# eBOOK-UPDATE_v3.net
KiCad netlist of a schematic drawn in EAGLE
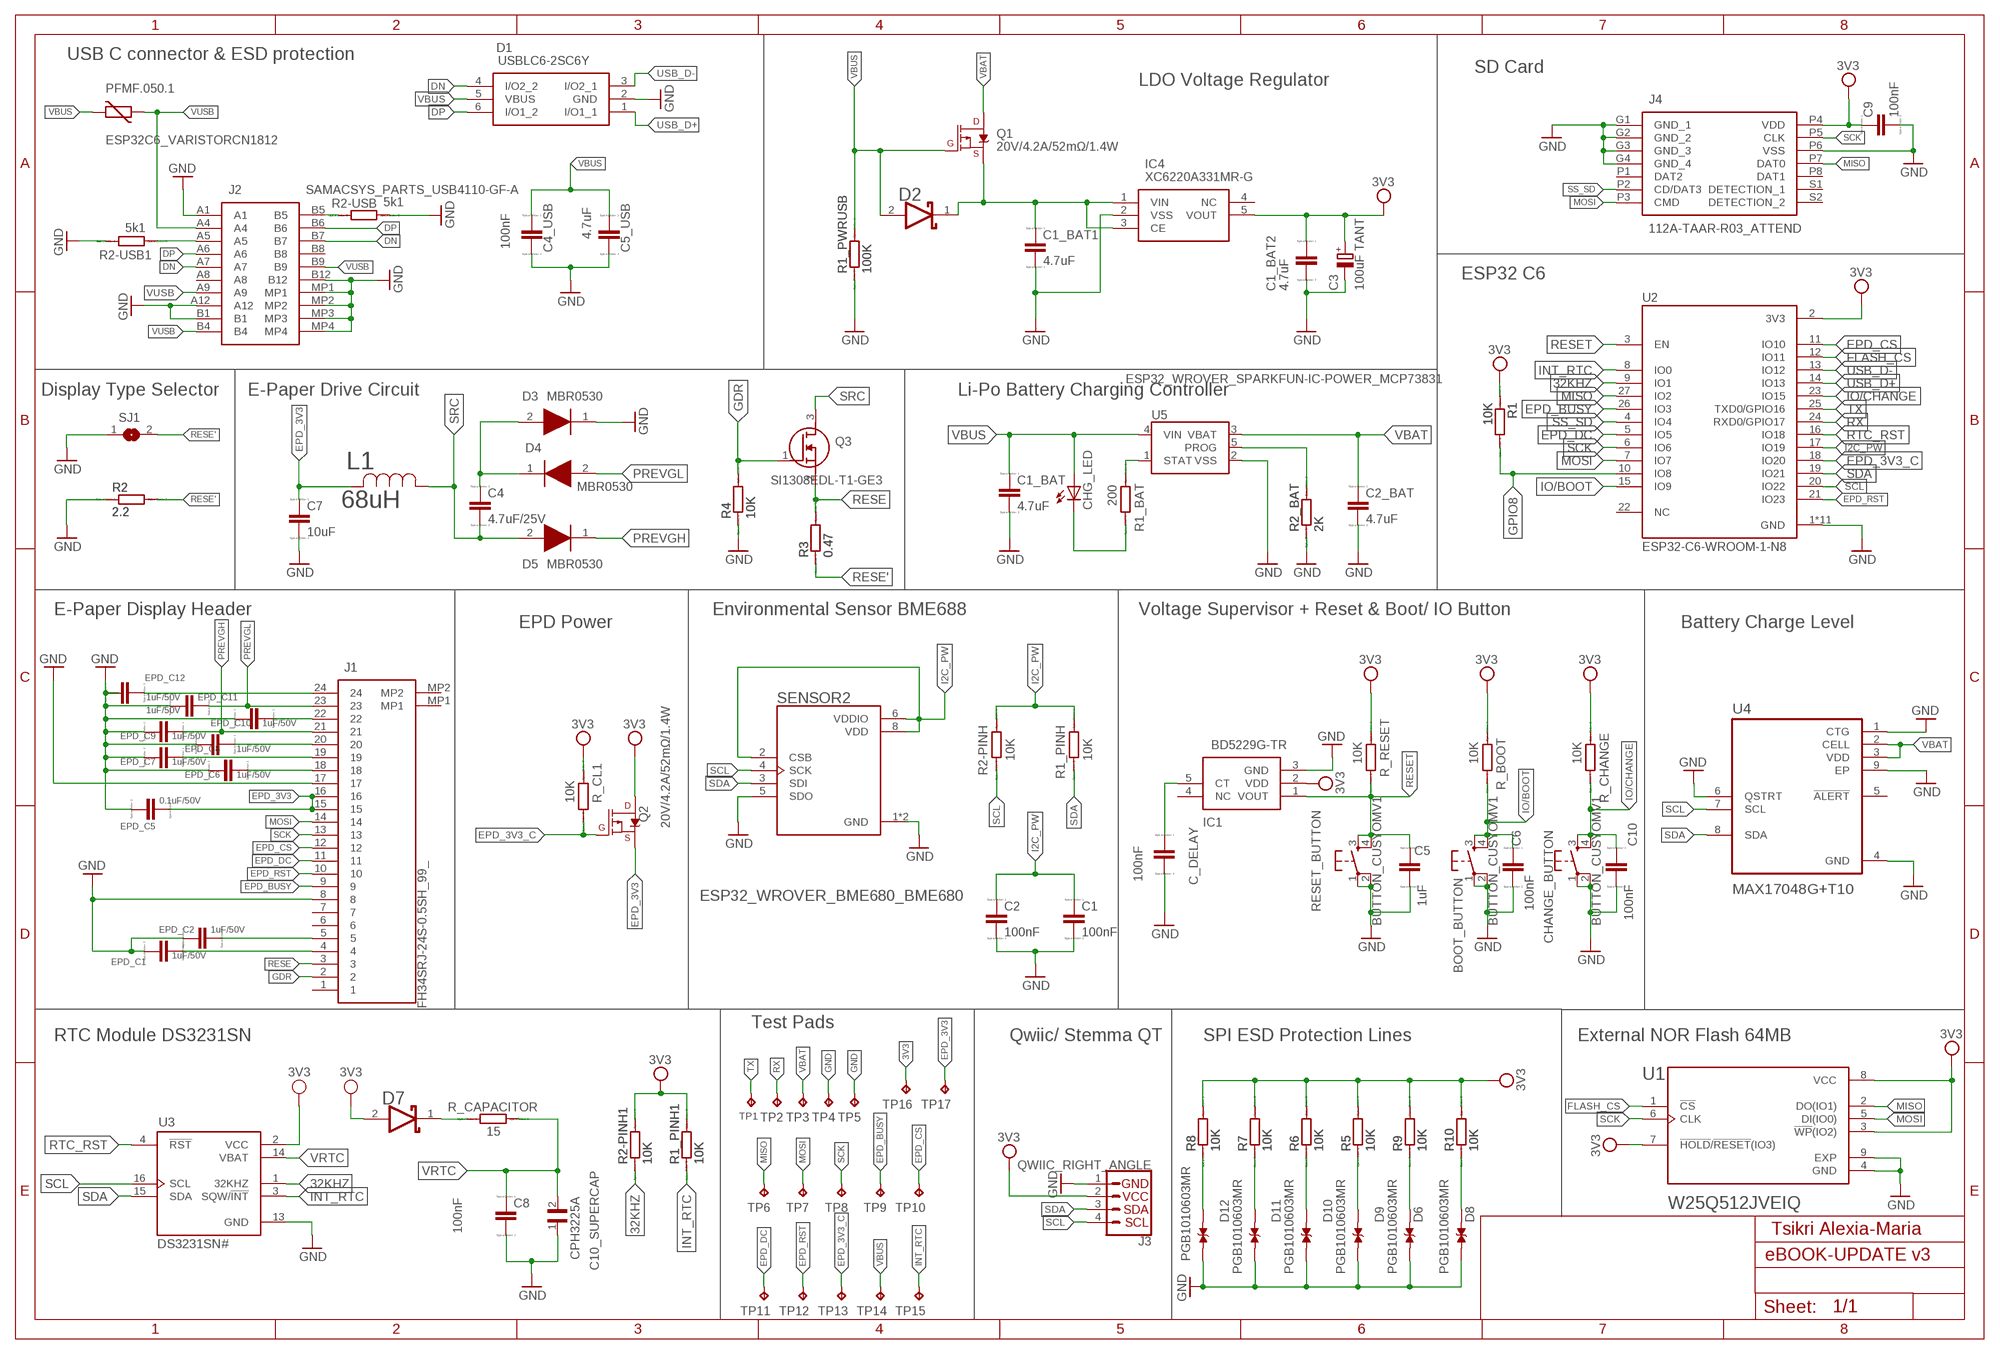
[diagram p0: schematic, sheet 1]

(export (version "E")
  (design (tool "Eeschema 10.0.6"))
  (components
    (comp (ref "BOOT_BUTTON")
      (value "BUTTON_CUSYOMV1")
      (footprint "eagle-import:MYBUTTON")
      (libsource (lib "eagle-import") (part "BUTTON_CUSYOMV1"))
    )
    (comp (ref "C1")
      (value "100nF")
      (footprint "eagle-import:ESP32_WROVER_EAGLE-LTSPICE_C0402")
      (libsource (lib "eagle-import") (part "ESP32_WROVER_EAGLE-LTSPICE_CC0402"))
    )
    (comp (ref "C1_BAT")
      (value "4.7uF")
      (footprint "eagle-import:ESP32_WROVER_EAGLE-LTSPICE_C0402")
      (libsource (lib "eagle-import") (part "ESP32_WROVER_EAGLE-LTSPICE_CC0402"))
    )
    (comp (ref "C1_BAT1")
      (value "4.7uF")
      (footprint "eagle-import:ESP32_WROVER_EAGLE-LTSPICE_C0402")
      (libsource (lib "eagle-import") (part "ESP32_WROVER_EAGLE-LTSPICE_CC0402"))
    )
    (comp (ref "C1_BAT2")
      (value "4.7uF")
      (footprint "eagle-import:ESP32_WROVER_EAGLE-LTSPICE_C0402")
      (libsource (lib "eagle-import") (part "ESP32_WROVER_EAGLE-LTSPICE_CC0402"))
    )
    (comp (ref "C2")
      (value "100nF")
      (footprint "eagle-import:ESP32_WROVER_EAGLE-LTSPICE_C0402")
      (libsource (lib "eagle-import") (part "ESP32_WROVER_EAGLE-LTSPICE_CC0402"))
    )
    (comp (ref "C2_BAT")
      (value "4.7uF")
      (footprint "eagle-import:ESP32_WROVER_EAGLE-LTSPICE_C0402")
      (libsource (lib "eagle-import") (part "ESP32_WROVER_EAGLE-LTSPICE_CC0402"))
    )
    (comp (ref "C3")
      (value "100uF TANT")
      (footprint "eagle-import:RCL_CT3528")
      (libsource (lib "eagle-import") (part "RCL_CPOL-EUCT3528"))
    )
    (comp (ref "C4")
      (value "4.7uF/25V")
      (footprint "eagle-import:ESP32_WROVER_EAGLE-LTSPICE_C0402")
      (libsource (lib "eagle-import") (part "ESP32_WROVER_EAGLE-LTSPICE_CC0402"))
    )
    (comp (ref "C4_USB")
      (value "100nF")
      (footprint "eagle-import:ESP32_WROVER_EAGLE-LTSPICE_C0402")
      (libsource (lib "eagle-import") (part "ESP32_WROVER_EAGLE-LTSPICE_CC0402"))
    )
    (comp (ref "C5")
      (value "1uF")
      (footprint "eagle-import:ESP32_WROVER_EAGLE-LTSPICE_C0402")
      (libsource (lib "eagle-import") (part "ESP32_WROVER_EAGLE-LTSPICE_CC0402"))
    )
    (comp (ref "C5_USB")
      (value "4.7uF")
      (footprint "eagle-import:ESP32_WROVER_EAGLE-LTSPICE_C0402")
      (libsource (lib "eagle-import") (part "ESP32_WROVER_EAGLE-LTSPICE_CC0402"))
    )
    (comp (ref "C6")
      (value "100nF")
      (footprint "eagle-import:ESP32_WROVER_EAGLE-LTSPICE_C0402")
      (libsource (lib "eagle-import") (part "ESP32_WROVER_EAGLE-LTSPICE_CC0402"))
    )
    (comp (ref "C7")
      (value "10uF")
      (footprint "eagle-import:ESP32_WROVER_EAGLE-LTSPICE_C0402")
      (libsource (lib "eagle-import") (part "ESP32_WROVER_EAGLE-LTSPICE_CC0402"))
    )
    (comp (ref "C8")
      (value "100nF")
      (footprint "eagle-import:ESP32_WROVER_EAGLE-LTSPICE_C0402")
      (libsource (lib "eagle-import") (part "ESP32_WROVER_EAGLE-LTSPICE_CC0402"))
    )
    (comp (ref "C9")
      (value "100nF")
      (footprint "eagle-import:ESP32_WROVER_EAGLE-LTSPICE_C0402")
      (libsource (lib "eagle-import") (part "ESP32_WROVER_EAGLE-LTSPICE_CC0402"))
    )
    (comp (ref "C10")
      (value "100nF")
      (footprint "eagle-import:ESP32_WROVER_EAGLE-LTSPICE_C0402")
      (libsource (lib "eagle-import") (part "ESP32_WROVER_EAGLE-LTSPICE_CC0402"))
    )
    (comp (ref "C10_SUPERCAP")
      (value "CPH3225A")
      (footprint "eagle-import:CAPCP3225X100N")
      (fields (field (name "MF") "Seiko Instruments"))
      (libsource (lib "eagle-import") (part "CPH3225A"))
    )
    (comp (ref "CHANGE_BUTTON")
      (value "BUTTON_CUSYOMV1")
      (footprint "eagle-import:MYBUTTON")
      (libsource (lib "eagle-import") (part "BUTTON_CUSYOMV1"))
    )
    (comp (ref "CHG_LED")
      (value "ADAFRUIT_LEDCHIP-LED0603")
      (footprint "eagle-import:ADAFRUIT_CHIP-LED0603")
      (libsource (lib "eagle-import") (part "ADAFRUIT_LEDCHIP-LED0603"))
    )
    (comp (ref "C_DELAY")
      (value "100nF")
      (footprint "eagle-import:ESP32_WROVER_EAGLE-LTSPICE_C0402")
      (libsource (lib "eagle-import") (part "ESP32_WROVER_EAGLE-LTSPICE_CC0402"))
    )
    (comp (ref "D1")
      (value "USBLC6-2SC6Y")
      (footprint "eagle-import:SOT95P280X145-6N")
      (fields (field (name "MF") "STMicroelectronics"))
      (libsource (lib "eagle-import") (part "USBLC6-2SC6Y"))
    )
    (comp (ref "D2")
      (value "ESP32_WROVER_AVX---SD0805S020S1R0_AVX_SD0805S020S1R0_0_0AVX_SD0805S020S1R0_0_0")
      (footprint "eagle-import:ESP32_WROVER_AVX---SD0805S020S1R0_AVX_SD0805S020S1R0_0")
      (fields
        (field (name "DIGIKEY_PART_NUMBER") "478-7800-1-ND")
        (field (name "MF") "AVX")
        (field (name "MOUSER_PART_NUMBER") "581-SD0805S020S1R0")
      )
      (libsource (lib "eagle-import") (part "ESP32_WROVER_AVX---SD0805S020S1R0_AVX_SD0805S020S1R0_0_0AVX_SD0805S020S1R0_0_0"))
    )
    (comp (ref "D3")
      (value "MBR0530")
      (footprint "eagle-import:SOD3716X135N")
      (fields (field (name "MF") "ON Semiconductor"))
      (libsource (lib "eagle-import") (part "MBR0530"))
    )
    (comp (ref "D4")
      (value "MBR0530")
      (footprint "eagle-import:SOD3716X135N")
      (fields (field (name "MF") "ON Semiconductor"))
      (libsource (lib "eagle-import") (part "MBR0530"))
    )
    (comp (ref "D5")
      (value "MBR0530")
      (footprint "eagle-import:SOD3716X135N")
      (fields (field (name "MF") "ON Semiconductor"))
      (libsource (lib "eagle-import") (part "MBR0530"))
    )
    (comp (ref "D6")
      (value "PGB1010603MR")
      (footprint "eagle-import:DIOC1608X36N")
      (fields (field (name "MF") "Littelfuse Inc."))
      (libsource (lib "eagle-import") (part "PGB1010603MR"))
    )
    (comp (ref "D7")
      (value "ESP32_WROVER_AVX---SD0805S020S1R0_AVX_SD0805S020S1R0_0_0AVX_SD0805S020S1R0_0_0")
      (footprint "eagle-import:ESP32_WROVER_AVX---SD0805S020S1R0_AVX_SD0805S020S1R0_0")
      (fields
        (field (name "DIGIKEY_PART_NUMBER") "478-7800-1-ND")
        (field (name "MF") "AVX")
        (field (name "MOUSER_PART_NUMBER") "581-SD0805S020S1R0")
      )
      (libsource (lib "eagle-import") (part "ESP32_WROVER_AVX---SD0805S020S1R0_AVX_SD0805S020S1R0_0_0AVX_SD0805S020S1R0_0_0"))
    )
    (comp (ref "D8")
      (value "PGB1010603MR")
      (footprint "eagle-import:DIOC1608X36N")
      (fields (field (name "MF") "Littelfuse Inc."))
      (libsource (lib "eagle-import") (part "PGB1010603MR"))
    )
    (comp (ref "D9")
      (value "PGB1010603MR")
      (footprint "eagle-import:DIOC1608X36N")
      (fields (field (name "MF") "Littelfuse Inc."))
      (libsource (lib "eagle-import") (part "PGB1010603MR"))
    )
    (comp (ref "D10")
      (value "PGB1010603MR")
      (footprint "eagle-import:DIOC1608X36N")
      (fields (field (name "MF") "Littelfuse Inc."))
      (libsource (lib "eagle-import") (part "PGB1010603MR"))
    )
    (comp (ref "D11")
      (value "PGB1010603MR")
      (footprint "eagle-import:DIOC1608X36N")
      (fields (field (name "MF") "Littelfuse Inc."))
      (libsource (lib "eagle-import") (part "PGB1010603MR"))
    )
    (comp (ref "D12")
      (value "PGB1010603MR")
      (footprint "eagle-import:DIOC1608X36N")
      (fields (field (name "MF") "Littelfuse Inc."))
      (libsource (lib "eagle-import") (part "PGB1010603MR"))
    )
    (comp (ref "EPD_C1")
      (value "1uF/50V")
      (footprint "eagle-import:ESP32_WROVER_EAGLE-LTSPICE_C0402")
      (libsource (lib "eagle-import") (part "ESP32_WROVER_EAGLE-LTSPICE_CC0402"))
    )
    (comp (ref "EPD_C2")
      (value "1uF/50V")
      (footprint "eagle-import:ESP32_WROVER_EAGLE-LTSPICE_C0402")
      (libsource (lib "eagle-import") (part "ESP32_WROVER_EAGLE-LTSPICE_CC0402"))
    )
    (comp (ref "EPD_C5")
      (value "0.1uF/50V")
      (footprint "eagle-import:ESP32_WROVER_EAGLE-LTSPICE_C0402")
      (libsource (lib "eagle-import") (part "ESP32_WROVER_EAGLE-LTSPICE_CC0402"))
    )
    (comp (ref "EPD_C6")
      (value "1uF/50V")
      (footprint "eagle-import:ESP32_WROVER_EAGLE-LTSPICE_C0402")
      (libsource (lib "eagle-import") (part "ESP32_WROVER_EAGLE-LTSPICE_CC0402"))
    )
    (comp (ref "EPD_C7")
      (value "1uF/50V")
      (footprint "eagle-import:ESP32_WROVER_EAGLE-LTSPICE_C0402")
      (libsource (lib "eagle-import") (part "ESP32_WROVER_EAGLE-LTSPICE_CC0402"))
    )
    (comp (ref "EPD_C8")
      (value "1uF/50V")
      (footprint "eagle-import:ESP32_WROVER_EAGLE-LTSPICE_C0402")
      (libsource (lib "eagle-import") (part "ESP32_WROVER_EAGLE-LTSPICE_CC0402"))
    )
    (comp (ref "EPD_C9")
      (value "1uF/50V")
      (footprint "eagle-import:ESP32_WROVER_EAGLE-LTSPICE_C0402")
      (libsource (lib "eagle-import") (part "ESP32_WROVER_EAGLE-LTSPICE_CC0402"))
    )
    (comp (ref "EPD_C10")
      (value "1uF/50V")
      (footprint "eagle-import:ESP32_WROVER_EAGLE-LTSPICE_C0402")
      (libsource (lib "eagle-import") (part "ESP32_WROVER_EAGLE-LTSPICE_CC0402"))
    )
    (comp (ref "EPD_C11")
      (value "1uF/50V")
      (footprint "eagle-import:ESP32_WROVER_EAGLE-LTSPICE_C0402")
      (libsource (lib "eagle-import") (part "ESP32_WROVER_EAGLE-LTSPICE_CC0402"))
    )
    (comp (ref "EPD_C12")
      (value "1uF/50V")
      (footprint "eagle-import:ESP32_WROVER_EAGLE-LTSPICE_C0402")
      (libsource (lib "eagle-import") (part "ESP32_WROVER_EAGLE-LTSPICE_CC0402"))
    )
    (comp (ref "IC1")
      (value "BD5229G-TR")
      (footprint "eagle-import:SOT95P280X125-5N")
      (fields (field (name "MOUSER_PART_NUMBER") "755-BD5229G-TR"))
      (libsource (lib "eagle-import") (part "BD5229G-TR"))
    )
    (comp (ref "IC4")
      (value "XC6220A331MR-G")
      (footprint "eagle-import:SOT95P280X120-5N")
      (fields (field (name "MOUSER_PART_NUMBER") "865-XC6220A331MR-G"))
      (libsource (lib "eagle-import") (part "XC6220A331MR-G"))
    )
    (comp (ref "J1")
      (value "FH34SRJ-24S-0.5SH_99_")
      (footprint "eagle-import:FH34SRJ24S05SH99")
      (fields
        (field (name "MANUFACTURER_PART_NUMBER") "FH34SRJ-24S-0.5SH(99)")
        (field (name "MOUSER_PART_NUMBER") "798-FH34SRJ24S05SH99")
      )
      (libsource (lib "eagle-import") (part "FH34SRJ-24S-0.5SH_99_"))
    )
    (comp (ref "J2")
      (value "SAMACSYS_PARTS_USB4110-GF-A")
      (footprint "eagle-import:SAMACSYS_PARTS_USB4110GFA")
      (fields
        (field (name "MANUFACTURER_PART_NUMBER") "USB4110-GF-A")
        (field (name "MOUSER_PART_NUMBER") "640-USB4110-GF-A")
      )
      (libsource (lib "eagle-import") (part "SAMACSYS_PARTS_USB4110-GF-A"))
    )
    (comp (ref "J3")
      (value "QWIIC_RIGHT_ANGLE")
      (footprint "eagle-import:JST04_1MM_RA")
      (libsource (lib "eagle-import") (part "QWIIC_CONNECTORJS-1MM"))
    )
    (comp (ref "J4")
      (value "112A-TAAR-R03_ATTEND")
      (footprint "eagle-import:112ATAARR03ATTEND")
      (fields (field (name "MANUFACTURER_PART_NUMBER") "112A-TAAR-R03 ATTEND"))
      (libsource (lib "eagle-import") (part "112A-TAAR-R03_ATTEND"))
    )
    (comp (ref "L1")
      (value "68uH")
      (footprint "eagle-import:IND_4828-WE-TPC_WRE")
      (fields
        (field (name "MANUFACTURER_PART_NUMBER") "744043680")
        (field (name "COPYRIGHT") "Copyright (C) 2024 Ultra Librarian. All rights reserved.")
      )
      (libsource (lib "eagle-import") (part "744043680IND_4828-WE-TPC_WRE"))
    )
    (comp (ref "PFMF.050.1")
      (value "ESP32C6_VARISTORCN1812")
      (footprint "eagle-import:ESP32C6_VARISTOR_CT_CN1812")
      (libsource (lib "eagle-import") (part "ESP32C6_VARISTORCN1812"))
    )
    (comp (ref "Q1")
      (value "20V/4.2A/52mΩ/1.4W")
      (footprint "eagle-import:ESP32_WROVER_SPARKFUN-DISCRETESEMI_SOT23-3")
      (libsource (lib "eagle-import") (part "ESP32_WROVER_SPARKFUN-DISCRETESEMI_MOSFET_PCH-DMG2305UX-7"))
    )
    (comp (ref "Q2")
      (value "20V/4.2A/52mΩ/1.4W")
      (footprint "eagle-import:ESP32_WROVER_SPARKFUN-DISCRETESEMI_SOT23-3")
      (libsource (lib "eagle-import") (part "ESP32_WROVER_SPARKFUN-DISCRETESEMI_MOSFET_PCH-DMG2305UX-7"))
    )
    (comp (ref "Q3")
      (value "SI1308EDL-T1-GE3")
      (footprint "eagle-import:SOT65P210X110-3N")
      (fields (field (name "MF") "Vishay Siliconix"))
      (libsource (lib "eagle-import") (part "SI1308EDL-T1-GE3"))
    )
    (comp (ref "R1")
      (value "10K")
      (footprint "eagle-import:ESP32_WROVER_EAGLE-LTSPICE_R0402")
      (libsource (lib "eagle-import") (part "ESP32_WROVER_EAGLE-LTSPICE_RR0402"))
    )
    (comp (ref "R1_BAT")
      (value "200")
      (footprint "eagle-import:ESP32_WROVER_EAGLE-LTSPICE_R0402")
      (libsource (lib "eagle-import") (part "ESP32_WROVER_EAGLE-LTSPICE_RR0402"))
    )
    (comp (ref "R1_PINH")
      (value "10K")
      (footprint "eagle-import:ESP32_WROVER_EAGLE-LTSPICE_R0402")
      (libsource (lib "eagle-import") (part "ESP32_WROVER_EAGLE-LTSPICE_RR0402"))
    )
    (comp (ref "R1_PINH1")
      (value "10K")
      (footprint "eagle-import:ESP32_WROVER_EAGLE-LTSPICE_R0402")
      (libsource (lib "eagle-import") (part "ESP32_WROVER_EAGLE-LTSPICE_RR0402"))
    )
    (comp (ref "R1_PWRUSB")
      (value "100K")
      (footprint "eagle-import:ESP32_WROVER_EAGLE-LTSPICE_R0402")
      (libsource (lib "eagle-import") (part "ESP32_WROVER_EAGLE-LTSPICE_RR0402"))
    )
    (comp (ref "R2")
      (value "2.2")
      (footprint "eagle-import:ESP32_WROVER_EAGLE-LTSPICE_R0402")
      (libsource (lib "eagle-import") (part "ESP32_WROVER_EAGLE-LTSPICE_RR0402"))
    )
    (comp (ref "R2-PINH")
      (value "10K")
      (footprint "eagle-import:ESP32_WROVER_EAGLE-LTSPICE_R0402")
      (libsource (lib "eagle-import") (part "ESP32_WROVER_EAGLE-LTSPICE_RR0402"))
    )
    (comp (ref "R2-PINH1")
      (value "10K")
      (footprint "eagle-import:ESP32_WROVER_EAGLE-LTSPICE_R0402")
      (libsource (lib "eagle-import") (part "ESP32_WROVER_EAGLE-LTSPICE_RR0402"))
    )
    (comp (ref "R2-USB")
      (value "5k1")
      (footprint "eagle-import:ESP32_WROVER_EAGLE-LTSPICE_R0402")
      (libsource (lib "eagle-import") (part "ESP32_WROVER_EAGLE-LTSPICE_RR0402"))
    )
    (comp (ref "R2-USB1")
      (value "5k1")
      (footprint "eagle-import:ESP32_WROVER_EAGLE-LTSPICE_R0402")
      (libsource (lib "eagle-import") (part "ESP32_WROVER_EAGLE-LTSPICE_RR0402"))
    )
    (comp (ref "R2_BAT")
      (value "2K")
      (footprint "eagle-import:ESP32_WROVER_EAGLE-LTSPICE_R0402")
      (libsource (lib "eagle-import") (part "ESP32_WROVER_EAGLE-LTSPICE_RR0402"))
    )
    (comp (ref "R3")
      (value "0.47")
      (footprint "eagle-import:ESP32_WROVER_EAGLE-LTSPICE_R0402")
      (libsource (lib "eagle-import") (part "ESP32_WROVER_EAGLE-LTSPICE_RR0402"))
    )
    (comp (ref "R4")
      (value "10K")
      (footprint "eagle-import:ESP32_WROVER_EAGLE-LTSPICE_R0402")
      (libsource (lib "eagle-import") (part "ESP32_WROVER_EAGLE-LTSPICE_RR0402"))
    )
    (comp (ref "R5")
      (value "10K")
      (footprint "eagle-import:ESP32_WROVER_EAGLE-LTSPICE_R0402")
      (libsource (lib "eagle-import") (part "ESP32_WROVER_EAGLE-LTSPICE_RR0402"))
    )
    (comp (ref "R6")
      (value "10K")
      (footprint "eagle-import:ESP32_WROVER_EAGLE-LTSPICE_R0402")
      (libsource (lib "eagle-import") (part "ESP32_WROVER_EAGLE-LTSPICE_RR0402"))
    )
    (comp (ref "R7")
      (value "10K")
      (footprint "eagle-import:ESP32_WROVER_EAGLE-LTSPICE_R0402")
      (libsource (lib "eagle-import") (part "ESP32_WROVER_EAGLE-LTSPICE_RR0402"))
    )
    (comp (ref "R8")
      (value "10K")
      (footprint "eagle-import:ESP32_WROVER_EAGLE-LTSPICE_R0402")
      (libsource (lib "eagle-import") (part "ESP32_WROVER_EAGLE-LTSPICE_RR0402"))
    )
    (comp (ref "R9")
      (value "10K")
      (footprint "eagle-import:ESP32_WROVER_EAGLE-LTSPICE_R0402")
      (libsource (lib "eagle-import") (part "ESP32_WROVER_EAGLE-LTSPICE_RR0402"))
    )
    (comp (ref "R10")
      (value "10K")
      (footprint "eagle-import:ESP32_WROVER_EAGLE-LTSPICE_R0402")
      (libsource (lib "eagle-import") (part "ESP32_WROVER_EAGLE-LTSPICE_RR0402"))
    )
    (comp (ref "RESET_BUTTON")
      (value "BUTTON_CUSYOMV1")
      (footprint "eagle-import:MYBUTTON")
      (libsource (lib "eagle-import") (part "BUTTON_CUSYOMV1"))
    )
    (comp (ref "R_BOOT")
      (value "10K")
      (footprint "eagle-import:ESP32_WROVER_EAGLE-LTSPICE_R0402")
      (libsource (lib "eagle-import") (part "ESP32_WROVER_EAGLE-LTSPICE_RR0402"))
    )
    (comp (ref "R_CAPACITOR")
      (value "15")
      (footprint "eagle-import:ESP32_WROVER_EAGLE-LTSPICE_R0402")
      (libsource (lib "eagle-import") (part "ESP32_WROVER_EAGLE-LTSPICE_RR0402"))
    )
    (comp (ref "R_CHANGE")
      (value "10K")
      (footprint "eagle-import:ESP32_WROVER_EAGLE-LTSPICE_R0402")
      (libsource (lib "eagle-import") (part "ESP32_WROVER_EAGLE-LTSPICE_RR0402"))
    )
    (comp (ref "R_CL1")
      (value "10K")
      (footprint "eagle-import:ESP32_WROVER_EAGLE-LTSPICE_R0402")
      (libsource (lib "eagle-import") (part "ESP32_WROVER_EAGLE-LTSPICE_RR0402"))
    )
    (comp (ref "R_RESET")
      (value "10K")
      (footprint "eagle-import:ESP32_WROVER_EAGLE-LTSPICE_R0402")
      (libsource (lib "eagle-import") (part "ESP32_WROVER_EAGLE-LTSPICE_RR0402"))
    )
    (comp (ref "SENSOR2")
      (value "ESP32_WROVER_BME680_BME680")
      (footprint "eagle-import:ESP32_WROVER_BME680_PSON80P300X300X100-8N")
      (fields (field (name "MF") "Bosch Sensortec") (field (name "MP") "BME680"))
      (libsource (lib "eagle-import") (part "ESP32_WROVER_BME680_BME680"))
    )
    (comp (ref "SJ1") (value "SJ") (footprint "eagle-import:SJ") (libsource (lib "eagle-import") (part "SJ")))
    (comp (ref "TP1")
      (value "TPTP20R")
      (footprint "eagle-import:TP20R")
      (libsource (lib "eagle-import") (part "TPTP20R"))
    )
    (comp (ref "TP2")
      (value "TPTP20R")
      (footprint "eagle-import:TP20R")
      (libsource (lib "eagle-import") (part "TPTP20R"))
    )
    (comp (ref "TP3")
      (value "TPTP20R")
      (footprint "eagle-import:TP20R")
      (libsource (lib "eagle-import") (part "TPTP20R"))
    )
    (comp (ref "TP4")
      (value "TPTP20R")
      (footprint "eagle-import:TP20R")
      (libsource (lib "eagle-import") (part "TPTP20R"))
    )
    (comp (ref "TP5")
      (value "TPTP20R")
      (footprint "eagle-import:TP20R")
      (libsource (lib "eagle-import") (part "TPTP20R"))
    )
    (comp (ref "TP6")
      (value "TPTP20R")
      (footprint "eagle-import:TP20R")
      (libsource (lib "eagle-import") (part "TPTP20R"))
    )
    (comp (ref "TP7")
      (value "TPTP20R")
      (footprint "eagle-import:TP20R")
      (libsource (lib "eagle-import") (part "TPTP20R"))
    )
    (comp (ref "TP8")
      (value "TPTP20R")
      (footprint "eagle-import:TP20R")
      (libsource (lib "eagle-import") (part "TPTP20R"))
    )
    (comp (ref "TP9")
      (value "TPTP20R")
      (footprint "eagle-import:TP20R")
      (libsource (lib "eagle-import") (part "TPTP20R"))
    )
    (comp (ref "TP10")
      (value "TPTP20R")
      (footprint "eagle-import:TP20R")
      (libsource (lib "eagle-import") (part "TPTP20R"))
    )
    (comp (ref "TP11")
      (value "TPTP20R")
      (footprint "eagle-import:TP20R")
      (libsource (lib "eagle-import") (part "TPTP20R"))
    )
    (comp (ref "TP12")
      (value "TPTP20R")
      (footprint "eagle-import:TP20R")
      (libsource (lib "eagle-import") (part "TPTP20R"))
    )
    (comp (ref "TP13")
      (value "TPTP20R")
      (footprint "eagle-import:TP20R")
      (libsource (lib "eagle-import") (part "TPTP20R"))
    )
    (comp (ref "TP14")
      (value "TPTP20R")
      (footprint "eagle-import:TP20R")
      (libsource (lib "eagle-import") (part "TPTP20R"))
    )
    (comp (ref "TP15")
      (value "TPTP20R")
      (footprint "eagle-import:TP20R")
      (libsource (lib "eagle-import") (part "TPTP20R"))
    )
    (comp (ref "TP16")
      (value "TPTP20R")
      (footprint "eagle-import:TP20R")
      (libsource (lib "eagle-import") (part "TPTP20R"))
    )
    (comp (ref "TP17")
      (value "TPTP20R")
      (footprint "eagle-import:TP20R")
      (libsource (lib "eagle-import") (part "TPTP20R"))
    )
    (comp (ref "U1")
      (value "W25Q512JVEIQ")
      (footprint "eagle-import:SON127P600X800X80-9N")
      (fields (field (name "MF") "Winbond Electronics"))
      (libsource (lib "eagle-import") (part "W25Q512JVEIQ"))
    )
    (comp (ref "U2")
      (value "ESP32-C6-WROOM-1-N8")
      (footprint "eagle-import:XCVR_ESP32-C6-WROOM-1-N8")
      (fields (field (name "MF") "Espressif Systems"))
      (libsource (lib "eagle-import") (part "ESP32-C6-WROOM-1-N8"))
    )
    (comp (ref "U3")
      (value "DS3231SN#")
      (footprint "eagle-import:SOIC127P1032X265-16N")
      (fields (field (name "MF") "Maxim Integrated Products"))
      (libsource (lib "eagle-import") (part "DS3231SN#"))
    )
    (comp (ref "U4")
      (value "MAX17048G+T10")
      (footprint "eagle-import:SON50P200X200X80-9N")
      (fields (field (name "MF") "Analog Devices"))
      (libsource (lib "eagle-import") (part "MAX17048G+T10"))
    )
    (comp (ref "U5")
      (value "ESP32_WROVER_SPARKFUN-IC-POWER_MCP73831")
      (footprint "eagle-import:ESP32_WROVER_SPARKFUN-IC-POWER_SOT23-5")
      (libsource (lib "eagle-import") (part "ESP32_WROVER_SPARKFUN-IC-POWER_MCP73831"))
    )
  )
  (nets
    (net (code "1") (name "3V3") (class "Default")
      (node (ref "C1_BAT2") (pin "1") (pinfunction "1_1") (pintype "passive"))
      (node (ref "C3") (pin "+") (pinfunction "+_+") (pintype "passive"))
      (node (ref "C9") (pin "1") (pinfunction "1_1") (pintype "passive"))
      (node (ref "D7") (pin "2") (pinfunction "ANODE_2") (pintype "bidirectional"))
      (node (ref "IC1") (pin "2") (pinfunction "VDD_2") (pintype "bidirectional"))
      (node (ref "IC4") (pin "5") (pinfunction "VOUT_5") (pintype "bidirectional"))
      (node (ref "J3") (pin "2") (pinfunction "2_2") (pintype "power_in"))
      (node (ref "J4") (pin "P4") (pinfunction "VDD_P4") (pintype "bidirectional"))
      (node (ref "Q2") (pin "3") (pinfunction "D_3") (pintype "bidirectional"))
      (node (ref "R1") (pin "1") (pinfunction "1_1") (pintype "passive"))
      (node (ref "R10") (pin "2") (pinfunction "2_2") (pintype "passive"))
      (node (ref "R1_PINH1") (pin "2") (pinfunction "2_2") (pintype "passive"))
      (node (ref "R2-PINH1") (pin "2") (pinfunction "2_2") (pintype "passive"))
      (node (ref "R5") (pin "2") (pinfunction "2_2") (pintype "passive"))
      (node (ref "R6") (pin "2") (pinfunction "2_2") (pintype "passive"))
      (node (ref "R7") (pin "2") (pinfunction "2_2") (pintype "passive"))
      (node (ref "R8") (pin "2") (pinfunction "2_2") (pintype "passive"))
      (node (ref "R9") (pin "2") (pinfunction "2_2") (pintype "passive"))
      (node (ref "R_BOOT") (pin "2") (pinfunction "2_2") (pintype "passive"))
      (node (ref "R_CHANGE") (pin "2") (pinfunction "2_2") (pintype "passive"))
      (node (ref "R_CL1") (pin "2") (pinfunction "2_2") (pintype "passive"))
      (node (ref "R_RESET") (pin "2") (pinfunction "2_2") (pintype "passive"))
      (node (ref "TP16") (pin "TP") (pinfunction "TP_TP") (pintype "input"))
      (node (ref "U1") (pin "3") (pinfunction "~{WP}(IO2)_3") (pintype "bidirectional"))
      (node (ref "U1") (pin "7") (pinfunction "~{HOLD}/~{RESET}(IO3)_7") (pintype "bidirectional"))
      (node (ref "U1") (pin "8") (pinfunction "VCC_8") (pintype "power_in"))
      (node (ref "U2") (pin "2") (pinfunction "3V3_2") (pintype "power_in"))
      (node (ref "U3") (pin "2") (pinfunction "VCC_2") (pintype "power_in"))
    )
    (net (code "2") (name "32KHZ") (class "Default")
      (node (ref "R2-PINH1") (pin "1") (pinfunction "1_1") (pintype "passive"))
      (node (ref "U2") (pin "9") (pinfunction "IO1_9") (pintype "bidirectional"))
      (node (ref "U3") (pin "1") (pinfunction "32KHZ_1") (pintype "output"))
    )
    (net (code "3") (name "DN") (class "Default")
      (node (ref "D1") (pin "4") (pinfunction "I/O2_2_4") (pintype "bidirectional"))
      (node (ref "J2") (pin "A7") (pinfunction "A7_A7") (pintype "bidirectional"))
      (node (ref "J2") (pin "B7") (pinfunction "B7_B7") (pintype "bidirectional"))
    )
    (net (code "4") (name "DP") (class "Default")
      (node (ref "D1") (pin "6") (pinfunction "I/O1_2_6") (pintype "bidirectional"))
      (node (ref "J2") (pin "A6") (pinfunction "A6_A6") (pintype "bidirectional"))
      (node (ref "J2") (pin "B6") (pinfunction "B6_B6") (pintype "bidirectional"))
    )
    (net (code "5") (name "EPD_3V3") (class "Default")
      (node (ref "C7") (pin "1") (pinfunction "1_1") (pintype "passive"))
      (node (ref "EPD_C5") (pin "1") (pinfunction "1_1") (pintype "passive"))
      (node (ref "J1") (pin "15") (pinfunction "15_15") (pintype "bidirectional"))
      (node (ref "J1") (pin "16") (pinfunction "16_16") (pintype "bidirectional"))
      (node (ref "L1") (pin "2") (pinfunction "2_2") (pintype "passive"))
      (node (ref "Q2") (pin "2") (pinfunction "S_2") (pintype "bidirectional"))
      (node (ref "TP17") (pin "TP") (pinfunction "TP_TP") (pintype "input"))
    )
    (net (code "6") (name "EPD_3V3_C") (class "Default")
      (node (ref "Q2") (pin "1") (pinfunction "G_1") (pintype "bidirectional"))
      (node (ref "R_CL1") (pin "1") (pinfunction "1_1") (pintype "passive"))
      (node (ref "TP13") (pin "TP") (pinfunction "TP_TP") (pintype "input"))
      (node (ref "U2") (pin "18") (pinfunction "IO20_18") (pintype "bidirectional"))
    )
    (net (code "7") (name "EPD_BUSY") (class "Default")
      (node (ref "J1") (pin "9") (pinfunction "9_9") (pintype "bidirectional"))
      (node (ref "TP9") (pin "TP") (pinfunction "TP_TP") (pintype "input"))
      (node (ref "U2") (pin "26") (pinfunction "IO3_26") (pintype "bidirectional"))
    )
    (net (code "8") (name "EPD_CS") (class "Default")
      (node (ref "J1") (pin "12") (pinfunction "12_12") (pintype "bidirectional"))
      (node (ref "TP10") (pin "TP") (pinfunction "TP_TP") (pintype "input"))
      (node (ref "U2") (pin "11") (pinfunction "IO10_11") (pintype "bidirectional"))
    )
    (net (code "9") (name "EPD_DC") (class "Default")
      (node (ref "J1") (pin "11") (pinfunction "11_11") (pintype "bidirectional"))
      (node (ref "TP11") (pin "TP") (pinfunction "TP_TP") (pintype "input"))
      (node (ref "U2") (pin "5") (pinfunction "IO5_5") (pintype "bidirectional"))
    )
    (net (code "10") (name "EPD_RST") (class "Default")
      (node (ref "J1") (pin "10") (pinfunction "10_10") (pintype "bidirectional"))
      (node (ref "TP12") (pin "TP") (pinfunction "TP_TP") (pintype "input"))
      (node (ref "U2") (pin "21") (pinfunction "IO23_21") (pintype "bidirectional"))
    )
    (net (code "11") (name "FLASH_CS") (class "Default")
      (node (ref "U1") (pin "1") (pinfunction "~{CS}_1") (pintype "input"))
      (node (ref "U2") (pin "12") (pinfunction "IO11_12") (pintype "bidirectional"))
    )
    (net (code "12") (name "GDR") (class "Default")
      (node (ref "J1") (pin "2") (pinfunction "2_2") (pintype "bidirectional"))
      (node (ref "Q3") (pin "1") (pinfunction "G_1") (pintype "bidirectional"))
      (node (ref "R4") (pin "2") (pinfunction "2_2") (pintype "passive"))
    )
    (net (code "13") (name "GND") (class "Default")
      (node (ref "BOOT_BUTTON") (pin "1") (pinfunction "1_1") (pintype "passive"))
      (node (ref "BOOT_BUTTON") (pin "2") (pinfunction "2_2") (pintype "passive"))
      (node (ref "C1") (pin "2") (pinfunction "2_2") (pintype "passive"))
      (node (ref "C10") (pin "2") (pinfunction "2_2") (pintype "passive"))
      (node (ref "C10_SUPERCAP") (pin "1") (pinfunction "1_1") (pintype "passive"))
      (node (ref "C1_BAT") (pin "2") (pinfunction "2_2") (pintype "passive"))
      (node (ref "C1_BAT1") (pin "2") (pinfunction "2_2") (pintype "passive"))
      (node (ref "C1_BAT2") (pin "2") (pinfunction "2_2") (pintype "passive"))
      (node (ref "C2") (pin "2") (pinfunction "2_2") (pintype "passive"))
      (node (ref "C2_BAT") (pin "2") (pinfunction "2_2") (pintype "passive"))
      (node (ref "C3") (pin "-") (pinfunction "-_-") (pintype "passive"))
      (node (ref "C4_USB") (pin "2") (pinfunction "2_2") (pintype "passive"))
      (node (ref "C5") (pin "2") (pinfunction "2_2") (pintype "passive"))
      (node (ref "C5_USB") (pin "2") (pinfunction "2_2") (pintype "passive"))
      (node (ref "C6") (pin "2") (pinfunction "2_2") (pintype "passive"))
      (node (ref "C7") (pin "2") (pinfunction "2_2") (pintype "passive"))
      (node (ref "C8") (pin "2") (pinfunction "2_2") (pintype "passive"))
      (node (ref "C9") (pin "2") (pinfunction "2_2") (pintype "passive"))
      (node (ref "CHANGE_BUTTON") (pin "1") (pinfunction "1_1") (pintype "passive"))
      (node (ref "CHANGE_BUTTON") (pin "2") (pinfunction "2_2") (pintype "passive"))
      (node (ref "C_DELAY") (pin "2") (pinfunction "2_2") (pintype "passive"))
      (node (ref "D1") (pin "2") (pinfunction "GND_2") (pintype "bidirectional"))
      (node (ref "D10") (pin "1") (pinfunction "1_1") (pintype "passive"))
      (node (ref "D11") (pin "1") (pinfunction "1_1") (pintype "passive"))
      (node (ref "D12") (pin "1") (pinfunction "1_1") (pintype "passive"))
      (node (ref "D3") (pin "1") (pinfunction "K_1") (pintype "bidirectional"))
      (node (ref "D6") (pin "1") (pinfunction "1_1") (pintype "passive"))
      (node (ref "D8") (pin "1") (pinfunction "1_1") (pintype "passive"))
      (node (ref "D9") (pin "1") (pinfunction "1_1") (pintype "passive"))
      (node (ref "EPD_C1") (pin "2") (pinfunction "2_2") (pintype "passive"))
      (node (ref "EPD_C10") (pin "2") (pinfunction "2_2") (pintype "passive"))
      (node (ref "EPD_C11") (pin "2") (pinfunction "2_2") (pintype "passive"))
      (node (ref "EPD_C12") (pin "2") (pinfunction "2_2") (pintype "passive"))
      (node (ref "EPD_C2") (pin "2") (pinfunction "2_2") (pintype "passive"))
      (node (ref "EPD_C5") (pin "2") (pinfunction "2_2") (pintype "passive"))
      (node (ref "EPD_C6") (pin "2") (pinfunction "2_2") (pintype "passive"))
      (node (ref "EPD_C7") (pin "2") (pinfunction "2_2") (pintype "passive"))
      (node (ref "EPD_C8") (pin "2") (pinfunction "2_2") (pintype "passive"))
      (node (ref "EPD_C9") (pin "2") (pinfunction "2_2") (pintype "passive"))
      (node (ref "IC1") (pin "3") (pinfunction "GND_3") (pintype "bidirectional"))
      (node (ref "IC4") (pin "2") (pinfunction "VSS_2") (pintype "bidirectional"))
      (node (ref "J1") (pin "17") (pinfunction "17_17") (pintype "bidirectional"))
      (node (ref "J1") (pin "8") (pinfunction "8_8") (pintype "bidirectional"))
      (node (ref "J2") (pin "A1") (pinfunction "A1_A1") (pintype "bidirectional"))
      (node (ref "J2") (pin "A12") (pinfunction "A12_A12") (pintype "bidirectional"))
      (node (ref "J2") (pin "B1") (pinfunction "B1_B1") (pintype "bidirectional"))
      (node (ref "J2") (pin "B12") (pinfunction "B12_B12") (pintype "bidirectional"))
      (node (ref "J2") (pin "MP1") (pinfunction "MP1_MP1") (pintype "bidirectional"))
      (node (ref "J2") (pin "MP2") (pinfunction "MP2_MP2") (pintype "bidirectional"))
      (node (ref "J2") (pin "MP3") (pinfunction "MP3_MP3") (pintype "bidirectional"))
      (node (ref "J2") (pin "MP4") (pinfunction "MP4_MP4") (pintype "bidirectional"))
      (node (ref "J3") (pin "1") (pinfunction "1_1") (pintype "power_in"))
      (node (ref "J4") (pin "G1") (pinfunction "GND_1_G1") (pintype "bidirectional"))
      (node (ref "J4") (pin "G2") (pinfunction "GND_2_G2") (pintype "bidirectional"))
      (node (ref "J4") (pin "G3") (pinfunction "GND_3_G3") (pintype "bidirectional"))
      (node (ref "J4") (pin "G4") (pinfunction "GND_4_G4") (pintype "bidirectional"))
      (node (ref "J4") (pin "P6") (pinfunction "VSS_P6") (pintype "bidirectional"))
      (node (ref "R1_PWRUSB") (pin "1") (pinfunction "1_1") (pintype "passive"))
      (node (ref "R2") (pin "1") (pinfunction "1_1") (pintype "passive"))
      (node (ref "R2-USB") (pin "2") (pinfunction "2_2") (pintype "passive"))
      (node (ref "R2-USB1") (pin "1") (pinfunction "1_1") (pintype "passive"))
      (node (ref "R2_BAT") (pin "1") (pinfunction "1_1") (pintype "passive"))
      (node (ref "R4") (pin "1") (pinfunction "1_1") (pintype "passive"))
      (node (ref "RESET_BUTTON") (pin "1") (pinfunction "1_1") (pintype "passive"))
      (node (ref "RESET_BUTTON") (pin "2") (pinfunction "2_2") (pintype "passive"))
      (node (ref "SENSOR2") (pin "1") (pinfunction "GND_1") (pintype "power_in"))
      (node (ref "SENSOR2") (pin "5") (pinfunction "SDO_5") (pintype "bidirectional"))
      (node (ref "SENSOR2") (pin "7") (pinfunction "GND_7") (pintype "power_in"))
      (node (ref "SJ1") (pin "1") (pinfunction "1_1") (pintype "passive"))
      (node (ref "TP4") (pin "TP") (pinfunction "TP_TP") (pintype "input"))
      (node (ref "TP5") (pin "TP") (pinfunction "TP_TP") (pintype "input"))
      (node (ref "U1") (pin "4") (pinfunction "GND_4") (pintype "power_in"))
      (node (ref "U1") (pin "9") (pinfunction "EXP_9") (pintype "passive"))
      (node (ref "U2") (pin "1") (pinfunction "GND_1") (pintype "power_in"))
      (node (ref "U2") (pin "28") (pinfunction "GND_28") (pintype "power_in"))
      (node (ref "U2") (pin "29_1") (pinfunction "GND_29_1") (pintype "power_in"))
      (node (ref "U2") (pin "29_2") (pinfunction "GND_29_2") (pintype "power_in"))
      (node (ref "U2") (pin "29_3") (pinfunction "GND_29_3") (pintype "power_in"))
      (node (ref "U2") (pin "29_4") (pinfunction "GND_29_4") (pintype "power_in"))
      (node (ref "U2") (pin "29_5") (pinfunction "GND_29_5") (pintype "power_in"))
      (node (ref "U2") (pin "29_6") (pinfunction "GND_29_6") (pintype "power_in"))
      (node (ref "U2") (pin "29_7") (pinfunction "GND_29_7") (pintype "power_in"))
      (node (ref "U2") (pin "29_8") (pinfunction "GND_29_8") (pintype "power_in"))
      (node (ref "U2") (pin "29_9") (pinfunction "GND_29_9") (pintype "power_in"))
      (node (ref "U3") (pin "13") (pinfunction "GND_13") (pintype "power_in"))
      (node (ref "U4") (pin "1") (pinfunction "CTG_1") (pintype "power_in"))
      (node (ref "U4") (pin "4") (pinfunction "GND_4") (pintype "power_in"))
      (node (ref "U4") (pin "6") (pinfunction "QSTRT_6") (pintype "input"))
      (node (ref "U4") (pin "9") (pinfunction "EP_9") (pintype "power_in"))
      (node (ref "U5") (pin "2") (pinfunction "VSS_2") (pintype "power_in"))
    )
    (net (code "14") (name "GPIO8") (class "Default")
      (node (ref "R1") (pin "2") (pinfunction "2_2") (pintype "passive"))
      (node (ref "U2") (pin "10") (pinfunction "IO8_10") (pintype "bidirectional"))
    )
    (net (code "15") (name "I2C_PW") (class "Default")
      (node (ref "C1") (pin "1") (pinfunction "1_1") (pintype "passive"))
      (node (ref "C2") (pin "1") (pinfunction "1_1") (pintype "passive"))
      (node (ref "R1_PINH") (pin "1") (pinfunction "1_1") (pintype "passive"))
      (node (ref "R2-PINH") (pin "1") (pinfunction "1_1") (pintype "passive"))
      (node (ref "SENSOR2") (pin "2") (pinfunction "CSB_2") (pintype "input"))
      (node (ref "SENSOR2") (pin "6") (pinfunction "VDDIO_6") (pintype "power_in"))
      (node (ref "SENSOR2") (pin "8") (pinfunction "VDD_8") (pintype "power_in"))
      (node (ref "U2") (pin "17") (pinfunction "IO19_17") (pintype "bidirectional"))
    )
    (net (code "16") (name "INT_RTC") (class "Default")
      (node (ref "R1_PINH1") (pin "1") (pinfunction "1_1") (pintype "passive"))
      (node (ref "TP15") (pin "TP") (pinfunction "TP_TP") (pintype "input"))
      (node (ref "U2") (pin "8") (pinfunction "IO0_8") (pintype "bidirectional"))
      (node (ref "U3") (pin "3") (pinfunction "SQW/~{INT}_3") (pintype "output"))
    )
    (net (code "17") (name "IO{slash}BOOT") (class "Default")
      (node (ref "BOOT_BUTTON") (pin "3") (pinfunction "3_3") (pintype "passive"))
      (node (ref "BOOT_BUTTON") (pin "4") (pinfunction "4_4") (pintype "passive"))
      (node (ref "C6") (pin "1") (pinfunction "1_1") (pintype "passive"))
      (node (ref "R_BOOT") (pin "1") (pinfunction "1_1") (pintype "passive"))
      (node (ref "U2") (pin "15") (pinfunction "IO9_15") (pintype "bidirectional"))
    )
    (net (code "18") (name "IO{slash}CHANGE") (class "Default")
      (node (ref "C10") (pin "1") (pinfunction "1_1") (pintype "passive"))
      (node (ref "CHANGE_BUTTON") (pin "3") (pinfunction "3_3") (pintype "passive"))
      (node (ref "CHANGE_BUTTON") (pin "4") (pinfunction "4_4") (pintype "passive"))
      (node (ref "R_CHANGE") (pin "1") (pinfunction "1_1") (pintype "passive"))
      (node (ref "U2") (pin "23") (pinfunction "IO15_23") (pintype "bidirectional"))
    )
    (net (code "19") (name "MISO") (class "Default")
      (node (ref "J4") (pin "P7") (pinfunction "DAT0_P7") (pintype "bidirectional"))
      (node (ref "TP6") (pin "TP") (pinfunction "TP_TP") (pintype "input"))
      (node (ref "U1") (pin "2") (pinfunction "DO(IO1)_2") (pintype "bidirectional"))
      (node (ref "U2") (pin "27") (pinfunction "IO2_27") (pintype "bidirectional"))
    )
    (net (code "20") (name "MOSI") (class "Default")
      (node (ref "J1") (pin "14") (pinfunction "14_14") (pintype "bidirectional"))
      (node (ref "J4") (pin "P3") (pinfunction "CMD_P3") (pintype "bidirectional"))
      (node (ref "TP7") (pin "TP") (pinfunction "TP_TP") (pintype "input"))
      (node (ref "U1") (pin "5") (pinfunction "DI(IO0)_5") (pintype "bidirectional"))
      (node (ref "U2") (pin "7") (pinfunction "IO7_7") (pintype "bidirectional"))
    )
    (net (code "21") (name "Net-(CHG_LED-PadC)") (class "Default")
      (node (ref "CHG_LED") (pin "C") (pinfunction "C_C") (pintype "passive"))
      (node (ref "R1_BAT") (pin "1") (pinfunction "1_1") (pintype "passive"))
    )
    (net (code "22") (name "Net-(D2-CATHODE)") (class "Default")
      (node (ref "C1_BAT1") (pin "1") (pinfunction "1_1") (pintype "passive"))
      (node (ref "D2") (pin "1") (pinfunction "CATHODE_1") (pintype "bidirectional"))
      (node (ref "IC4") (pin "1") (pinfunction "VIN_1") (pintype "bidirectional"))
      (node (ref "IC4") (pin "3") (pinfunction "CE_3") (pintype "bidirectional"))
      (node (ref "Q1") (pin "2") (pinfunction "S_2") (pintype "bidirectional"))
    )
    (net (code "23") (name "Net-(D3-A)") (class "Default")
      (node (ref "C4") (pin "1") (pinfunction "1_1") (pintype "passive"))
      (node (ref "D3") (pin "2") (pinfunction "A_2") (pintype "bidirectional"))
      (node (ref "D4") (pin "1") (pinfunction "K_1") (pintype "bidirectional"))
    )
    (net (code "24") (name "Net-(D6-Pad2)") (class "Default")
      (node (ref "D6") (pin "2") (pinfunction "2_2") (pintype "passive"))
      (node (ref "R9") (pin "1") (pinfunction "1_1") (pintype "passive"))
    )
    (net (code "25") (name "Net-(D7-CATHODE)") (class "Default")
      (node (ref "D7") (pin "1") (pinfunction "CATHODE_1") (pintype "bidirectional"))
      (node (ref "R_CAPACITOR") (pin "1") (pinfunction "1_1") (pintype "passive"))
    )
    (net (code "26") (name "Net-(D8-Pad2)") (class "Default")
      (node (ref "D8") (pin "2") (pinfunction "2_2") (pintype "passive"))
      (node (ref "R10") (pin "1") (pinfunction "1_1") (pintype "passive"))
    )
    (net (code "27") (name "Net-(D9-Pad2)") (class "Default")
      (node (ref "D9") (pin "2") (pinfunction "2_2") (pintype "passive"))
      (node (ref "R5") (pin "1") (pinfunction "1_1") (pintype "passive"))
    )
    (net (code "28") (name "Net-(D10-Pad2)") (class "Default")
      (node (ref "D10") (pin "2") (pinfunction "2_2") (pintype "passive"))
      (node (ref "R6") (pin "1") (pinfunction "1_1") (pintype "passive"))
    )
    (net (code "29") (name "Net-(D11-Pad2)") (class "Default")
      (node (ref "D11") (pin "2") (pinfunction "2_2") (pintype "passive"))
      (node (ref "R7") (pin "1") (pinfunction "1_1") (pintype "passive"))
    )
    (net (code "30") (name "Net-(D12-Pad2)") (class "Default")
      (node (ref "D12") (pin "2") (pinfunction "2_2") (pintype "passive"))
      (node (ref "R8") (pin "1") (pinfunction "1_1") (pintype "passive"))
    )
    (net (code "31") (name "Net-(EPD_C1-Pad1)") (class "Default")
      (node (ref "EPD_C1") (pin "1") (pinfunction "1_1") (pintype "passive"))
      (node (ref "J1") (pin "4") (pinfunction "4_4") (pintype "bidirectional"))
    )
    (net (code "32") (name "Net-(EPD_C2-Pad1)") (class "Default")
      (node (ref "EPD_C2") (pin "1") (pinfunction "1_1") (pintype "passive"))
      (node (ref "J1") (pin "5") (pinfunction "5_5") (pintype "bidirectional"))
    )
    (net (code "33") (name "Net-(EPD_C6-Pad1)") (class "Default")
      (node (ref "EPD_C6") (pin "1") (pinfunction "1_1") (pintype "passive"))
      (node (ref "J1") (pin "18") (pinfunction "18_18") (pintype "bidirectional"))
    )
    (net (code "34") (name "Net-(EPD_C7-Pad1)") (class "Default")
      (node (ref "EPD_C7") (pin "1") (pinfunction "1_1") (pintype "passive"))
      (node (ref "J1") (pin "19") (pinfunction "19_19") (pintype "bidirectional"))
    )
    (net (code "35") (name "Net-(EPD_C8-Pad1)") (class "Default")
      (node (ref "EPD_C8") (pin "1") (pinfunction "1_1") (pintype "passive"))
      (node (ref "J1") (pin "20") (pinfunction "20_20") (pintype "bidirectional"))
    )
    (net (code "36") (name "Net-(EPD_C10-Pad1)") (class "Default")
      (node (ref "EPD_C10") (pin "1") (pinfunction "1_1") (pintype "passive"))
      (node (ref "J1") (pin "22") (pinfunction "22_22") (pintype "bidirectional"))
    )
    (net (code "37") (name "Net-(EPD_C12-Pad1)") (class "Default")
      (node (ref "EPD_C12") (pin "1") (pinfunction "1_1") (pintype "passive"))
      (node (ref "J1") (pin "24") (pinfunction "24_24") (pintype "bidirectional"))
    )
    (net (code "38") (name "Net-(IC1-CT)") (class "Default")
      (node (ref "C_DELAY") (pin "1") (pinfunction "1_1") (pintype "passive"))
      (node (ref "IC1") (pin "5") (pinfunction "CT_5") (pintype "bidirectional"))
    )
    (net (code "39") (name "Net-(J2-PadA5)") (class "Default")
      (node (ref "J2") (pin "A5") (pinfunction "A5_A5") (pintype "bidirectional"))
      (node (ref "R2-USB1") (pin "2") (pinfunction "2_2") (pintype "passive"))
    )
    (net (code "40") (name "Net-(J2-PadB5)") (class "Default")
      (node (ref "J2") (pin "B5") (pinfunction "B5_B5") (pintype "bidirectional"))
      (node (ref "R2-USB") (pin "1") (pinfunction "1_1") (pintype "passive"))
    )
    (net (code "41") (name "Net-(U5-PROG)") (class "Default")
      (node (ref "R2_BAT") (pin "2") (pinfunction "2_2") (pintype "passive"))
      (node (ref "U5") (pin "5") (pinfunction "PROG_5") (pintype "input"))
    )
    (net (code "42") (name "Net-(U5-STAT)") (class "Default")
      (node (ref "R1_BAT") (pin "2") (pinfunction "2_2") (pintype "passive"))
      (node (ref "U5") (pin "1") (pinfunction "STAT_1") (pintype "output"))
    )
    (net (code "43") (name "PREVGH") (class "Default")
      (node (ref "D5") (pin "1") (pinfunction "K_1") (pintype "bidirectional"))
      (node (ref "EPD_C9") (pin "1") (pinfunction "1_1") (pintype "passive"))
      (node (ref "J1") (pin "21") (pinfunction "21_21") (pintype "bidirectional"))
    )
    (net (code "44") (name "PREVGL") (class "Default")
      (node (ref "D4") (pin "2") (pinfunction "A_2") (pintype "bidirectional"))
      (node (ref "EPD_C11") (pin "1") (pinfunction "1_1") (pintype "passive"))
      (node (ref "J1") (pin "23") (pinfunction "23_23") (pintype "bidirectional"))
    )
    (net (code "45") (name "RESE") (class "Default")
      (node (ref "J1") (pin "3") (pinfunction "3_3") (pintype "bidirectional"))
      (node (ref "Q3") (pin "2") (pinfunction "S_2") (pintype "bidirectional"))
      (node (ref "R3") (pin "2") (pinfunction "2_2") (pintype "passive"))
    )
    (net (code "46") (name "RESE'") (class "Default")
      (node (ref "R2") (pin "2") (pinfunction "2_2") (pintype "passive"))
      (node (ref "R3") (pin "1") (pinfunction "1_1") (pintype "passive"))
      (node (ref "SJ1") (pin "2") (pinfunction "2_2") (pintype "passive"))
    )
    (net (code "47") (name "RESET") (class "Default")
      (node (ref "C5") (pin "1") (pinfunction "1_1") (pintype "passive"))
      (node (ref "IC1") (pin "1") (pinfunction "VOUT_1") (pintype "bidirectional"))
      (node (ref "RESET_BUTTON") (pin "3") (pinfunction "3_3") (pintype "passive"))
      (node (ref "RESET_BUTTON") (pin "4") (pinfunction "4_4") (pintype "passive"))
      (node (ref "R_RESET") (pin "1") (pinfunction "1_1") (pintype "passive"))
      (node (ref "U2") (pin "3") (pinfunction "EN_3") (pintype "input"))
    )
    (net (code "48") (name "RTC_RST") (class "Default")
      (node (ref "U2") (pin "16") (pinfunction "IO18_16") (pintype "bidirectional"))
      (node (ref "U3") (pin "4") (pinfunction "~{RST}_4") (pintype "input"))
    )
    (net (code "49") (name "RX") (class "Default")
      (node (ref "TP2") (pin "TP") (pinfunction "TP_TP") (pintype "input"))
      (node (ref "U2") (pin "24") (pinfunction "RXD0/GPIO17_24") (pintype "bidirectional"))
    )
    (net (code "50") (name "SCK") (class "Default")
      (node (ref "J1") (pin "13") (pinfunction "13_13") (pintype "bidirectional"))
      (node (ref "J4") (pin "P5") (pinfunction "CLK_P5") (pintype "bidirectional"))
      (node (ref "TP8") (pin "TP") (pinfunction "TP_TP") (pintype "input"))
      (node (ref "U1") (pin "6") (pinfunction "CLK_6") (pintype "input"))
      (node (ref "U2") (pin "6") (pinfunction "IO6_6") (pintype "bidirectional"))
    )
    (net (code "51") (name "SCL") (class "Default")
      (node (ref "J3") (pin "4") (pinfunction "4_4") (pintype "passive"))
      (node (ref "R2-PINH") (pin "2") (pinfunction "2_2") (pintype "passive"))
      (node (ref "SENSOR2") (pin "4") (pinfunction "SCK_4") (pintype "input"))
      (node (ref "U2") (pin "20") (pinfunction "IO22_20") (pintype "bidirectional"))
      (node (ref "U3") (pin "16") (pinfunction "SCL_16") (pintype "input"))
      (node (ref "U4") (pin "7") (pinfunction "SCL_7") (pintype "input"))
    )
    (net (code "52") (name "SDA") (class "Default")
      (node (ref "J3") (pin "3") (pinfunction "3_3") (pintype "passive"))
      (node (ref "R1_PINH") (pin "2") (pinfunction "2_2") (pintype "passive"))
      (node (ref "SENSOR2") (pin "3") (pinfunction "SDI_3") (pintype "bidirectional"))
      (node (ref "U2") (pin "19") (pinfunction "IO21_19") (pintype "bidirectional"))
      (node (ref "U3") (pin "15") (pinfunction "SDA_15") (pintype "bidirectional"))
      (node (ref "U4") (pin "8") (pinfunction "SDA_8") (pintype "bidirectional"))
    )
    (net (code "53") (name "SRC") (class "Default")
      (node (ref "C4") (pin "2") (pinfunction "2_2") (pintype "passive"))
      (node (ref "D5") (pin "2") (pinfunction "A_2") (pintype "bidirectional"))
      (node (ref "L1") (pin "1") (pinfunction "1_1") (pintype "passive"))
      (node (ref "Q3") (pin "3") (pinfunction "D_3") (pintype "bidirectional"))
    )
    (net (code "54") (name "SS_SD") (class "Default")
      (node (ref "J4") (pin "P2") (pinfunction "CD/DAT3_P2") (pintype "bidirectional"))
      (node (ref "U2") (pin "4") (pinfunction "IO4_4") (pintype "bidirectional"))
    )
    (net (code "55") (name "TX") (class "Default")
      (node (ref "TP1") (pin "TP") (pinfunction "TP_TP") (pintype "input"))
      (node (ref "U2") (pin "25") (pinfunction "TXD0/GPIO16_25") (pintype "bidirectional"))
    )
    (net (code "56") (name "USB_D+") (class "Default")
      (node (ref "D1") (pin "1") (pinfunction "I/O1_1_1") (pintype "bidirectional"))
      (node (ref "U2") (pin "14") (pinfunction "IO13_14") (pintype "bidirectional"))
    )
    (net (code "57") (name "USB_D-") (class "Default")
      (node (ref "D1") (pin "3") (pinfunction "I/O2_1_3") (pintype "bidirectional"))
      (node (ref "U2") (pin "13") (pinfunction "IO12_13") (pintype "bidirectional"))
    )
    (net (code "58") (name "VBAT") (class "Default")
      (node (ref "C2_BAT") (pin "1") (pinfunction "1_1") (pintype "passive"))
      (node (ref "Q1") (pin "3") (pinfunction "D_3") (pintype "bidirectional"))
      (node (ref "TP3") (pin "TP") (pinfunction "TP_TP") (pintype "input"))
      (node (ref "U4") (pin "2") (pinfunction "CELL_2") (pintype "power_in"))
      (node (ref "U4") (pin "3") (pinfunction "VDD_3") (pintype "power_in"))
      (node (ref "U5") (pin "3") (pinfunction "VBAT_3") (pintype "power_in"))
    )
    (net (code "59") (name "VBUS") (class "Default")
      (node (ref "C1_BAT") (pin "1") (pinfunction "1_1") (pintype "passive"))
      (node (ref "C4_USB") (pin "1") (pinfunction "1_1") (pintype "passive"))
      (node (ref "C5_USB") (pin "1") (pinfunction "1_1") (pintype "passive"))
      (node (ref "CHG_LED") (pin "A") (pinfunction "A_A") (pintype "passive"))
      (node (ref "D1") (pin "5") (pinfunction "VBUS_5") (pintype "bidirectional"))
      (node (ref "D2") (pin "2") (pinfunction "ANODE_2") (pintype "bidirectional"))
      (node (ref "PFMF.050.1") (pin "2") (pinfunction "2_2") (pintype "passive"))
      (node (ref "Q1") (pin "1") (pinfunction "G_1") (pintype "bidirectional"))
      (node (ref "R1_PWRUSB") (pin "2") (pinfunction "2_2") (pintype "passive"))
      (node (ref "TP14") (pin "TP") (pinfunction "TP_TP") (pintype "input"))
      (node (ref "U5") (pin "4") (pinfunction "VIN_4") (pintype "power_in"))
    )
    (net (code "60") (name "VRTC") (class "Default")
      (node (ref "C10_SUPERCAP") (pin "2") (pinfunction "2_2") (pintype "passive"))
      (node (ref "C8") (pin "1") (pinfunction "1_1") (pintype "passive"))
      (node (ref "R_CAPACITOR") (pin "2") (pinfunction "2_2") (pintype "passive"))
      (node (ref "U3") (pin "14") (pinfunction "VBAT_14") (pintype "power_in"))
    )
    (net (code "61") (name "VUSB") (class "Default")
      (node (ref "J2") (pin "A4") (pinfunction "A4_A4") (pintype "bidirectional"))
      (node (ref "J2") (pin "A9") (pinfunction "A9_A9") (pintype "bidirectional"))
      (node (ref "J2") (pin "B4") (pinfunction "B4_B4") (pintype "bidirectional"))
      (node (ref "J2") (pin "B9") (pinfunction "B9_B9") (pintype "bidirectional"))
      (node (ref "PFMF.050.1") (pin "1") (pinfunction "1_1") (pintype "passive"))
    )
    (net (code "62") (name "unconnected-(IC1-NC-Pad4)") (class "Default")
      (node (ref "IC1") (pin "4") (pinfunction "NC_4") (pintype "no_connect"))
    )
    (net (code "63") (name "unconnected-(IC4-NC-Pad4)") (class "Default")
      (node (ref "IC4") (pin "4") (pinfunction "NC_4") (pintype "no_connect"))
    )
    (net (code "64") (name "unconnected-(J1-Pad1)") (class "Default")
      (node (ref "J1") (pin "1") (pinfunction "1_1") (pintype "bidirectional"))
    )
    (net (code "65") (name "unconnected-(J1-Pad6)") (class "Default")
      (node (ref "J1") (pin "6") (pinfunction "6_6") (pintype "bidirectional"))
    )
    (net (code "66") (name "unconnected-(J1-Pad7)") (class "Default")
      (node (ref "J1") (pin "7") (pinfunction "7_7") (pintype "bidirectional"))
    )
    (net (code "67") (name "unconnected-(J1-PadMP1)") (class "Default")
      (node (ref "J1") (pin "MP1") (pinfunction "MP1_MP1") (pintype "bidirectional"))
    )
    (net (code "68") (name "unconnected-(J1-PadMP2)") (class "Default")
      (node (ref "J1") (pin "MP2") (pinfunction "MP2_MP2") (pintype "bidirectional"))
    )
    (net (code "69") (name "unconnected-(J2-PadA8)") (class "Default")
      (node (ref "J2") (pin "A8") (pinfunction "A8_A8") (pintype "bidirectional"))
    )
    (net (code "70") (name "unconnected-(J2-PadB8)") (class "Default")
      (node (ref "J2") (pin "B8") (pinfunction "B8_B8") (pintype "bidirectional"))
    )
    (net (code "71") (name "unconnected-(J4-DAT1-PadP8)") (class "Default")
      (node (ref "J4") (pin "P8") (pinfunction "DAT1_P8") (pintype "bidirectional"))
    )
    (net (code "72") (name "unconnected-(J4-DAT2-PadP1)") (class "Default")
      (node (ref "J4") (pin "P1") (pinfunction "DAT2_P1") (pintype "bidirectional"))
    )
    (net (code "73") (name "unconnected-(J4-DETECTION_1-PadS1)") (class "Default")
      (node (ref "J4") (pin "S1") (pinfunction "DETECTION_1_S1") (pintype "bidirectional"))
    )
    (net (code "74") (name "unconnected-(J4-DETECTION_2-PadS2)") (class "Default")
      (node (ref "J4") (pin "S2") (pinfunction "DETECTION_2_S2") (pintype "bidirectional"))
    )
    (net (code "75") (name "unconnected-(U2-NC-Pad22)") (class "Default")
      (node (ref "U2") (pin "22") (pinfunction "NC_22") (pintype "no_connect"))
    )
    (net (code "76") (name "unconnected-(U4-~{ALERT}-Pad5)") (class "Default")
      (node (ref "U4") (pin "5") (pinfunction "~{ALERT}_5") (pintype "output"))
    )
  )
)
